# INA240_Breakout.net
KiCad netlist of a schematic drawn in Altium Designer
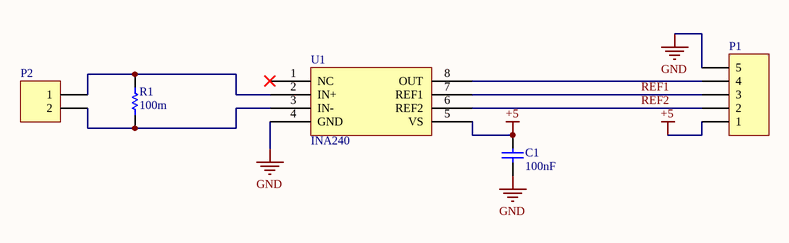
[diagram p0: INA240_Breakout.SchDoc]

(export (version "E")
  (design (tool "Eeschema 10.0.6"))
  (components
    (comp (ref "C1")
      (value "100nF")
      (footprint "0805 - Capacitor")
      (description "Nonpolarized Capacitor")
      (fields
        (field (name "MANUFACTURER") "Yageo")
        (field (name "MANUFACTURER PART NUMBER") "CC0805KRX7R9BB104")
      )
      (libsource (lib "General") (part "Capacitor - Nonpolarized"))
    )
    (comp (ref "P1")
      (value "1x5 Header")
      (footprint "HDR1X5")
      (description "1x5 Pin Header")
      (libsource (lib "GeneralConnectors") (part "1x5 Header"))
    )
    (comp (ref "P2")
      (value "1x2 Header")
      (footprint "HDR1X2")
      (description "1x2 Pin Header")
      (libsource (lib "GeneralConnectors") (part "1x2 Header"))
    )
    (comp (ref "R1")
      (value "100m")
      (footprint "0805 - Resistor")
      (description "Resistor")
      (fields (field (name "MANUFACTURER PART NUMBER") "73L3R10J") (field (name "MANUFACTURER") "CTS"))
      (libsource (lib "General") (part "Resistor"))
    )
    (comp (ref "U1")
      (value "INA240")
      (footprint "INA240")
      (description "-4V to 80V Current Sense Amplifier")
      (fields
        (field (name "MANUFACTURER") "Texas Instruments")
        (field (name "MANUFACTURER PART NUMBER") "INA240A2DR")
      )
      (libsource (lib "GeneralComponents") (part "INA240"))
    )
  )
  (nets
    (net (code "1") (name "+5") (class "Default")
      (node (ref "C1") (pin "2") (pinfunction "2_2") (pintype "passive"))
      (node (ref "P1") (pin "1") (pinfunction "1_1") (pintype "passive"))
      (node (ref "U1") (pin "5") (pinfunction "VS_5") (pintype "power_in"))
    )
    (net (code "2") (name "/REF1") (class "Default")
      (node (ref "P1") (pin "3") (pinfunction "3_3") (pintype "passive"))
      (node (ref "U1") (pin "7") (pinfunction "REF1_7") (pintype "passive"))
    )
    (net (code "3") (name "/REF2") (class "Default")
      (node (ref "P1") (pin "2") (pinfunction "2_2") (pintype "passive"))
      (node (ref "U1") (pin "6") (pinfunction "REF2_6") (pintype "passive"))
    )
    (net (code "4") (name "GND") (class "Default")
      (node (ref "C1") (pin "1") (pinfunction "1_1") (pintype "passive"))
      (node (ref "P1") (pin "5") (pinfunction "5_5") (pintype "passive"))
      (node (ref "U1") (pin "4") (pinfunction "GND_4") (pintype "power_in"))
    )
    (net (code "5") (name "Net-(U1-IN+)") (class "Default")
      (node (ref "P2") (pin "1") (pinfunction "1_1") (pintype "passive"))
      (node (ref "R1") (pin "1") (pinfunction "1_1") (pintype "passive"))
      (node (ref "U1") (pin "2") (pinfunction "IN+_2") (pintype "passive"))
    )
    (net (code "6") (name "Net-(U1-IN-)") (class "Default")
      (node (ref "P2") (pin "2") (pinfunction "2_2") (pintype "passive"))
      (node (ref "R1") (pin "2") (pinfunction "2_2") (pintype "passive"))
      (node (ref "U1") (pin "3") (pinfunction "IN-_3") (pintype "passive"))
    )
    (net (code "7") (name "Net-(U1-OUT)") (class "Default")
      (node (ref "P1") (pin "4") (pinfunction "4_4") (pintype "passive"))
      (node (ref "U1") (pin "8") (pinfunction "OUT_8") (pintype "passive"))
    )
    (net (code "8") (name "unconnected-(U1-NC-Pad1)") (class "Default")
      (node (ref "U1") (pin "1") (pinfunction "NC_1") (pintype "passive+no_connect"))
    )
  )
)
